# POWER_STAGE.net
KiCad netlist of a schematic drawn in Altium Designer
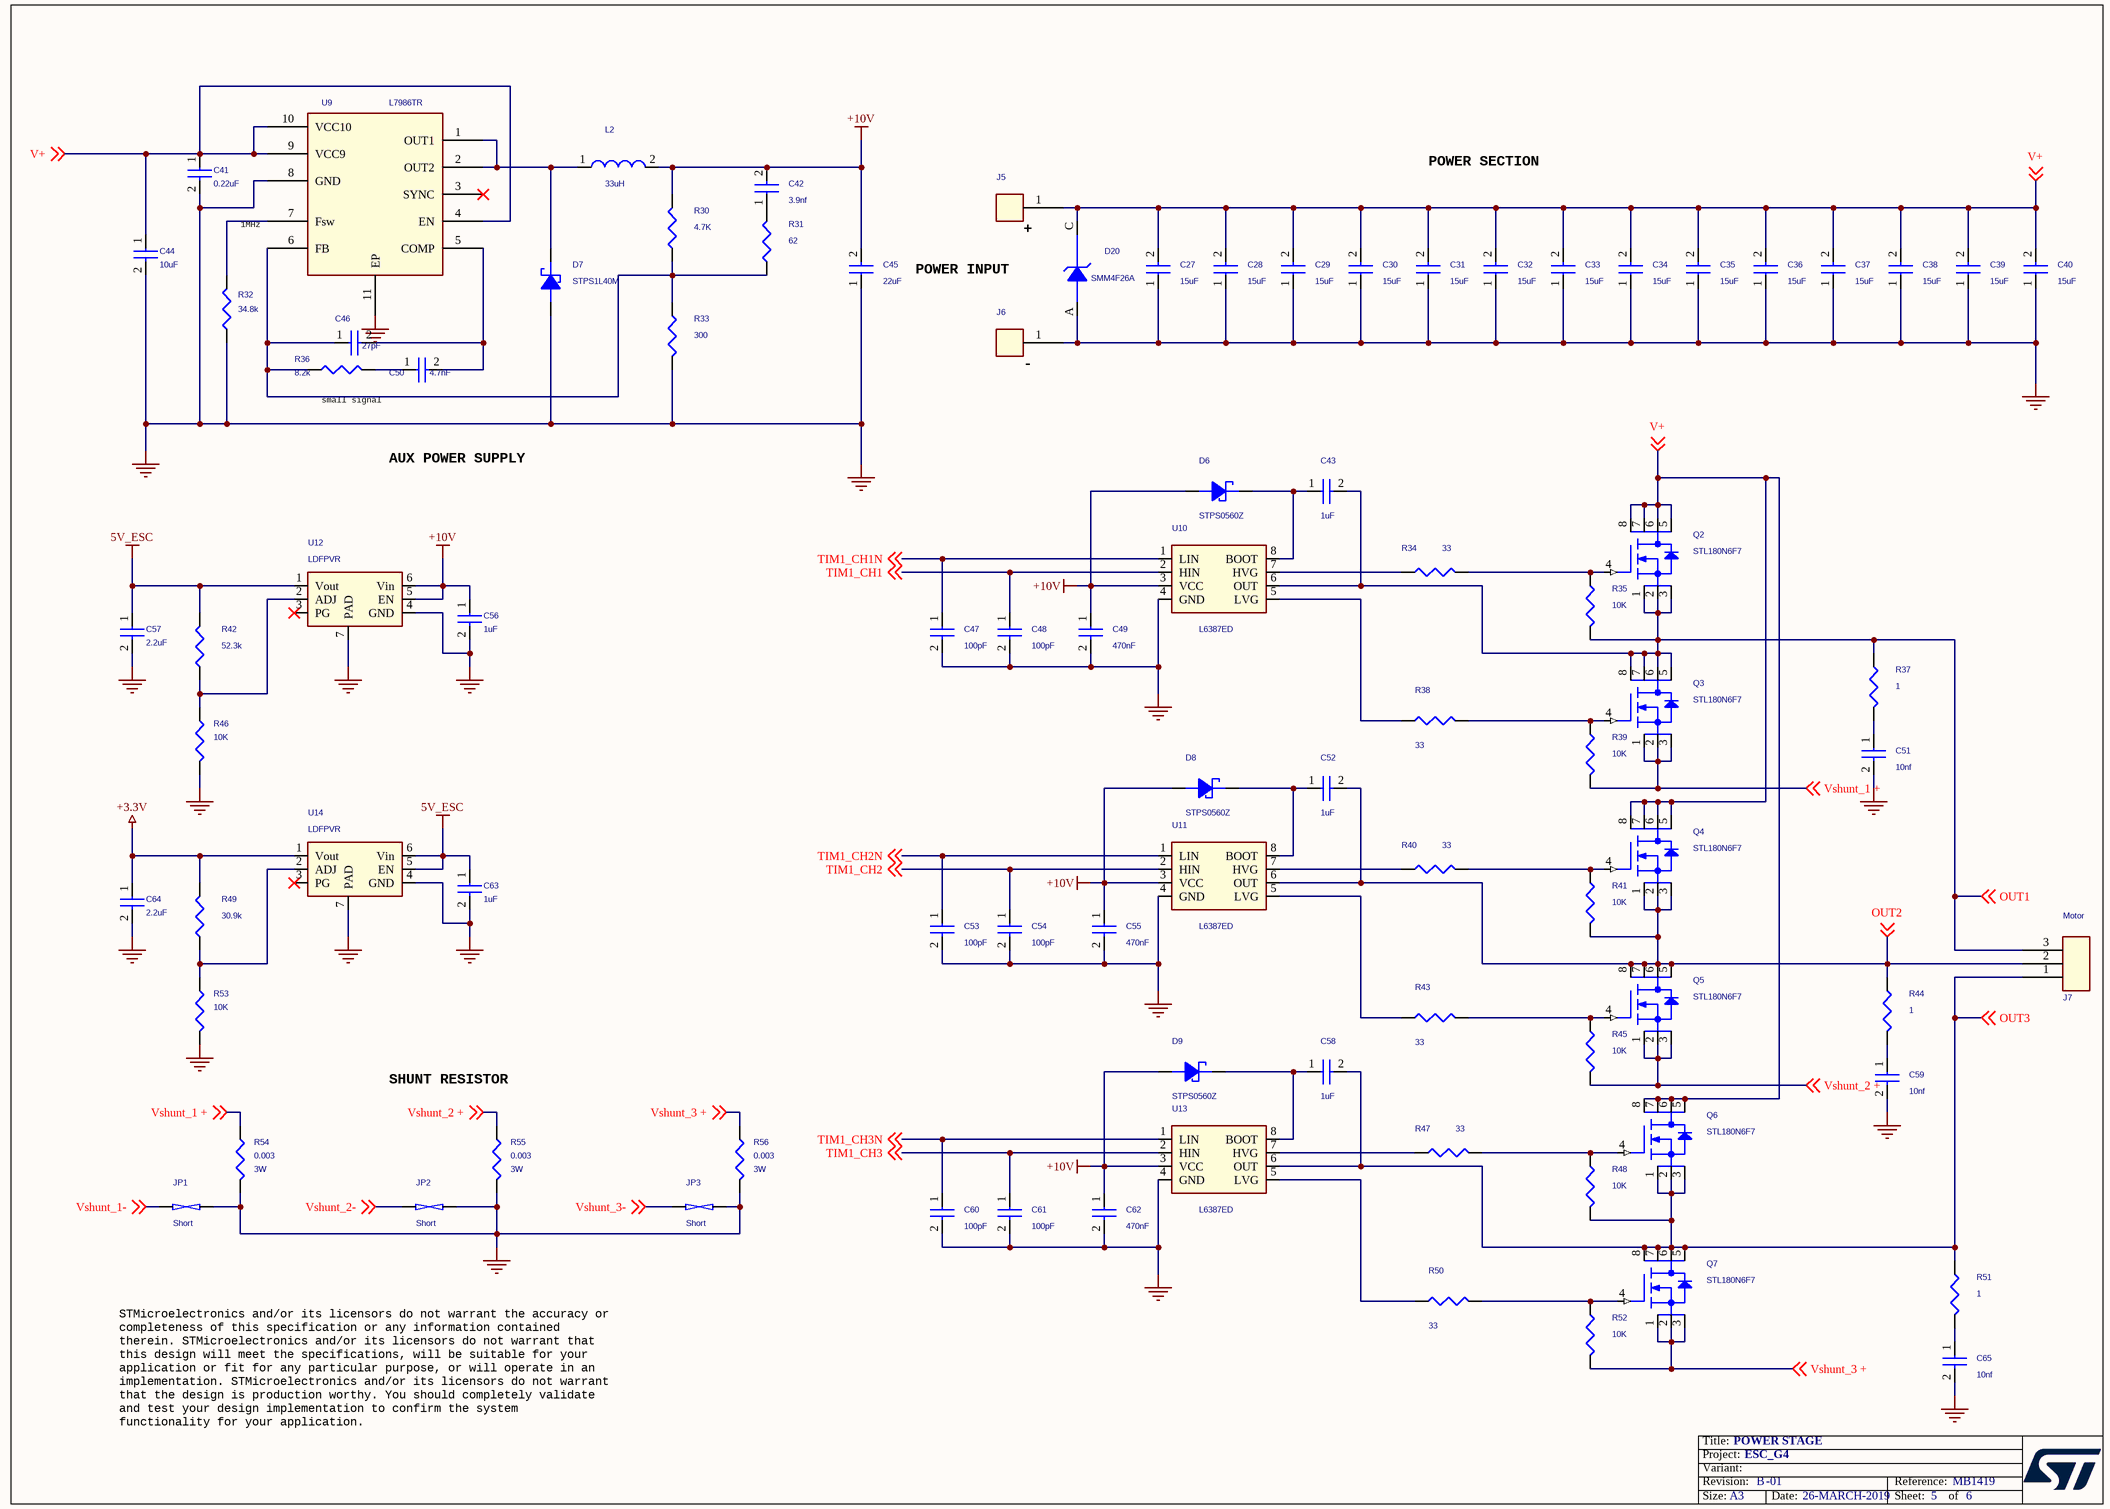
[diagram p0: POWER STAGE.SchDoc]

(export (version "E")
  (design (tool "Eeschema 10.0.6"))
  (components
    (comp (ref "C27")
      (value "15uF")
      (footprint "C_0805_HD")
      (description "CAP CER 15UF 35V X5R 0805")
      (fields (field (name "PART_NUMBER") "TMP-773") (field (name "TOLERANCE") "20%"))
      (libsource (lib "*") (part "CAP_Dup1"))
    )
    (comp (ref "C28")
      (value "15uF")
      (footprint "C_0805_HD")
      (description "CAP CER 15UF 35V X5R 0805")
      (fields (field (name "PART_NUMBER") "TMP-773") (field (name "TOLERANCE") "20%"))
      (libsource (lib "*") (part "CAP_Dup1"))
    )
    (comp (ref "C29")
      (value "15uF")
      (footprint "C_0805_HD")
      (description "CAP CER 15UF 35V X5R 0805")
      (fields (field (name "PART_NUMBER") "TMP-773") (field (name "TOLERANCE") "20%"))
      (libsource (lib "*") (part "CAP_Dup1"))
    )
    (comp (ref "C30")
      (value "15uF")
      (footprint "C_0805_HD")
      (description "CAP CER 15UF 35V X5R 0805")
      (fields (field (name "PART_NUMBER") "TMP-773") (field (name "TOLERANCE") "20%"))
      (libsource (lib "*") (part "CAP_Dup1"))
    )
    (comp (ref "C31")
      (value "15uF")
      (footprint "C_0805_HD")
      (description "CAP CER 15UF 35V X5R 0805")
      (fields (field (name "PART_NUMBER") "TMP-773") (field (name "TOLERANCE") "20%"))
      (libsource (lib "*") (part "CAP_Dup1"))
    )
    (comp (ref "C32")
      (value "15uF")
      (footprint "C_0805_HD")
      (description "CAP CER 15UF 35V X5R 0805")
      (fields (field (name "PART_NUMBER") "TMP-773") (field (name "TOLERANCE") "20%"))
      (libsource (lib "*") (part "CAP_Dup1"))
    )
    (comp (ref "C33")
      (value "15uF")
      (footprint "C_0805_HD")
      (description "CAP CER 15UF 35V X5R 0805")
      (fields (field (name "PART_NUMBER") "TMP-773") (field (name "TOLERANCE") "20%"))
      (libsource (lib "*") (part "CAP_Dup1"))
    )
    (comp (ref "C34")
      (value "15uF")
      (footprint "C_0805_HD")
      (description "CAP CER 15UF 35V X5R 0805")
      (fields (field (name "PART_NUMBER") "TMP-773") (field (name "TOLERANCE") "20%"))
      (libsource (lib "*") (part "CAP_Dup1"))
    )
    (comp (ref "C35")
      (value "15uF")
      (footprint "C_0805_HD")
      (description "CAP CER 15UF 35V X5R 0805")
      (fields (field (name "PART_NUMBER") "TMP-773") (field (name "TOLERANCE") "20%"))
      (libsource (lib "*") (part "CAP_Dup1"))
    )
    (comp (ref "C36")
      (value "15uF")
      (footprint "C_0805_HD")
      (description "CAP CER 15UF 35V X5R 0805")
      (fields (field (name "PART_NUMBER") "TMP-773") (field (name "TOLERANCE") "20%"))
      (libsource (lib "*") (part "CAP_Dup1"))
    )
    (comp (ref "C37")
      (value "15uF")
      (footprint "C_0805_HD")
      (description "CAP CER 15UF 35V X5R 0805")
      (fields (field (name "PART_NUMBER") "TMP-773") (field (name "TOLERANCE") "20%"))
      (libsource (lib "*") (part "CAP_Dup1"))
    )
    (comp (ref "C38")
      (value "15uF")
      (footprint "C_0805_HD")
      (description "CAP CER 15UF 35V X5R 0805")
      (fields (field (name "PART_NUMBER") "TMP-773") (field (name "TOLERANCE") "20%"))
      (libsource (lib "*") (part "CAP_Dup1"))
    )
    (comp (ref "C39")
      (value "15uF")
      (footprint "C_0805_HD")
      (description "CAP CER 15UF 35V X5R 0805")
      (fields (field (name "PART_NUMBER") "TMP-773") (field (name "TOLERANCE") "20%"))
      (libsource (lib "*") (part "CAP_Dup1"))
    )
    (comp (ref "C40")
      (value "15uF")
      (footprint "C_0805_HD")
      (description "CAP CER 15UF 35V X5R 0805")
      (fields (field (name "PART_NUMBER") "TMP-773") (field (name "TOLERANCE") "20%"))
      (libsource (lib "*") (part "CAP_Dup1"))
    )
    (comp (ref "C41")
      (value "0.22uF")
      (footprint "C_0603_HD")
      (description "CAP CER 0.22UF 50V X7R 0603")
      (fields (field (name "MANUFACTURER") "TDK Corporation") (field (name "TOLERANCE") "10%"))
      (libsource (lib "*") (part "CAP_Dup1"))
    )
    (comp (ref "C42")
      (value "3.9nf")
      (footprint "C_0402")
      (description "CAP CER 3900PF 16V X7R 0402")
      (fields (field (name "MANUFACTURER") "KEMET") (field (name "TOLERANCE") "10%"))
      (libsource (lib "*") (part "CAP_Dup1"))
    )
    (comp (ref "C43")
      (value "1uF")
      (footprint "C_0603_HD")
      (description "CAP CER 1UF 25V X7R 0603")
      (fields (field (name "PART_NUMBER") "TMP-446") (field (name "TOLERANCE") "10%"))
      (libsource (lib "*") (part "CAP_Dup1"))
    )
    (comp (ref "C44")
      (value "10uF")
      (footprint "C_1206")
      (description "CAP CER 10UF 50V X7R 1206")
      (fields
        (field (name "MANUFACTURER") "Samsung Electro-Mechanics America, Inc.")
        (field (name "TOLERANCE") "10%")
      )
      (libsource (lib "*") (part "CAP_Dup1"))
    )
    (comp (ref "C45")
      (value "22uF")
      (footprint "C_1206")
      (description "CAP CER 22UF 25V X5R 1206")
      (fields
        (field (name "MANUFACTURER") "Murata Electronics North America")
        (field (name "TOLERANCE") "20%")
      )
      (libsource (lib "*") (part "CAP_Dup1"))
    )
    (comp (ref "C46")
      (value "27pF")
      (footprint "C_0402")
      (description "CAP CER 27PF 25V C0G/NP0 0402")
      (fields
        (field (name "MANUFACTURER") "Murata Electronics North America")
        (field (name "TOLERANCE") "5%")
      )
      (libsource (lib "*") (part "CAP_Dup1"))
    )
    (comp (ref "C47")
      (value "100pF")
      (footprint "C_0402")
      (description "CAP CER 100PF 25V X7R 0402")
      (fields (field (name "PART_NUMBER") "TMP-426") (field (name "TOLERANCE") "10%"))
      (libsource (lib "*") (part "CAP_Dup1"))
    )
    (comp (ref "C48")
      (value "100pF")
      (footprint "C_0402")
      (description "CAP CER 100PF 25V X7R 0402")
      (fields (field (name "PART_NUMBER") "TMP-426") (field (name "TOLERANCE") "10%"))
      (libsource (lib "*") (part "CAP_Dup1"))
    )
    (comp (ref "C49")
      (value "470nF")
      (footprint "C_0603_HD")
      (description "CAP CER 0.47UF 25V X7R 0603")
      (fields (field (name "PART_NUMBER") "TMP-428") (field (name "TOLERANCE") "10%"))
      (libsource (lib "*") (part "CAP_Dup1"))
    )
    (comp (ref "C50")
      (value "4.7nF")
      (footprint "C_0402")
      (description "CAP CER 4700PF 16V X7R 0402")
      (fields (field (name "MANUFACTURER") "Wurth Electronics Inc.") (field (name "TOLERANCE") "10%"))
      (libsource (lib "*") (part "CAP_Dup1"))
    )
    (comp (ref "C51")
      (value "10nf")
      (footprint "C_0603")
      (description "CAP CER 10000PF 100V X7R 0603")
      (fields (field (name "PART_NUMBER") "CAP-00000040") (field (name "TOLERANCE") "20%"))
      (libsource (lib "*") (part "CAP_Dup1"))
    )
    (comp (ref "C52")
      (value "1uF")
      (footprint "C_0603_HD")
      (description "CAP CER 1UF 25V X7R 0603")
      (fields (field (name "PART_NUMBER") "TMP-446") (field (name "TOLERANCE") "10%"))
      (libsource (lib "*") (part "CAP_Dup1"))
    )
    (comp (ref "C53")
      (value "100pF")
      (footprint "C_0402")
      (description "CAP CER 100PF 25V X7R 0402")
      (fields (field (name "PART_NUMBER") "TMP-426") (field (name "TOLERANCE") "10%"))
      (libsource (lib "*") (part "CAP_Dup1"))
    )
    (comp (ref "C54")
      (value "100pF")
      (footprint "C_0402")
      (description "CAP CER 100PF 25V X7R 0402")
      (fields (field (name "PART_NUMBER") "TMP-426") (field (name "TOLERANCE") "10%"))
      (libsource (lib "*") (part "CAP_Dup1"))
    )
    (comp (ref "C55")
      (value "470nF")
      (footprint "C_0603_HD")
      (description "CAP CER 0.47UF 25V X7R 0603")
      (fields (field (name "PART_NUMBER") "TMP-428") (field (name "TOLERANCE") "10%"))
      (libsource (lib "*") (part "CAP_Dup1"))
    )
    (comp (ref "C56")
      (value "1uF")
      (footprint "C_0402")
      (description "CAP CER 1UF 25V X5R 0402")
      (fields
        (field (name "MANUFACTURER") "Murata Electronics North America")
        (field (name "TOLERANCE") "10%")
      )
      (libsource (lib "*") (part "CAP_Dup1"))
    )
    (comp (ref "C57")
      (value "2.2uF")
      (footprint "C_0402")
      (description "CAP CER 2.2UF 10V X5R 0402")
      (fields (field (name "PART_NUMBER") "TMP-449") (field (name "TOLERANCE") "20%"))
      (libsource (lib "*") (part "CAP_Dup1"))
    )
    (comp (ref "C58")
      (value "1uF")
      (footprint "C_0603_HD")
      (description "CAP CER 1UF 25V X7R 0603")
      (fields (field (name "PART_NUMBER") "TMP-446") (field (name "TOLERANCE") "10%"))
      (libsource (lib "*") (part "CAP_Dup1"))
    )
    (comp (ref "C59")
      (value "10nf")
      (footprint "C_0603")
      (description "CAP CER 10000PF 100V X7R 0603")
      (fields (field (name "PART_NUMBER") "CAP-00000040") (field (name "TOLERANCE") "20%"))
      (libsource (lib "*") (part "CAP_Dup1"))
    )
    (comp (ref "C60")
      (value "100pF")
      (footprint "C_0402")
      (description "CAP CER 100PF 25V X7R 0402")
      (fields (field (name "PART_NUMBER") "TMP-426") (field (name "TOLERANCE") "10%"))
      (libsource (lib "*") (part "CAP_Dup1"))
    )
    (comp (ref "C61")
      (value "100pF")
      (footprint "C_0402")
      (description "CAP CER 100PF 25V X7R 0402")
      (fields (field (name "PART_NUMBER") "TMP-426") (field (name "TOLERANCE") "10%"))
      (libsource (lib "*") (part "CAP_Dup1"))
    )
    (comp (ref "C62")
      (value "470nF")
      (footprint "C_0603_HD")
      (description "CAP CER 0.47UF 25V X7R 0603")
      (fields (field (name "PART_NUMBER") "TMP-428") (field (name "TOLERANCE") "10%"))
      (libsource (lib "*") (part "CAP_Dup1"))
    )
    (comp (ref "C63")
      (value "1uF")
      (footprint "C_0402")
      (description "CAP CER 1UF 25V X5R 0402")
      (fields
        (field (name "MANUFACTURER") "Murata Electronics North America")
        (field (name "TOLERANCE") "10%")
      )
      (libsource (lib "*") (part "CAP_Dup1"))
    )
    (comp (ref "C64")
      (value "2.2uF")
      (footprint "C_0402")
      (description "CAP CER 2.2UF 10V X5R 0402")
      (fields (field (name "PART_NUMBER") "TMP-449") (field (name "TOLERANCE") "20%"))
      (libsource (lib "*") (part "CAP_Dup1"))
    )
    (comp (ref "C65")
      (value "10nf")
      (footprint "C_0603")
      (description "CAP CER 10000PF 100V X7R 0603")
      (fields (field (name "PART_NUMBER") "CAP-00000040") (field (name "TOLERANCE") "20%"))
      (libsource (lib "*") (part "CAP_Dup1"))
    )
    (comp (ref "D6")
      (value "STPS0560Z")
      (footprint "SOD_123")
      (description "DIODE SCHOTTKY 60V 500MA SOD123")
      (fields (field (name "MANUFACTURER") "STMicroelectronics") (field (name "PART_NUMBER") "TMP-373"))
      (libsource (lib "*") (part "DIODE_SCHOTTKY_0"))
    )
    (comp (ref "D7")
      (value "STPS1L40M")
      (footprint "do216-aa_stmite")
      (description "DIODE SCHOTTKY 40V 1A STMITE")
      (fields (field (name "PART_NUMBER") "TMP-372") (field (name "MANUFACTURER") "STMicroelectronics"))
      (libsource (lib "*") (part "DIODE_SCHOTTKY_0"))
    )
    (comp (ref "D8")
      (value "STPS0560Z")
      (footprint "SOD_123")
      (description "DIODE SCHOTTKY 60V 500MA SOD123")
      (fields (field (name "MANUFACTURER") "STMicroelectronics") (field (name "PART_NUMBER") "TMP-373"))
      (libsource (lib "*") (part "DIODE_SCHOTTKY_0"))
    )
    (comp (ref "D9")
      (value "STPS0560Z")
      (footprint "SOD_123")
      (description "DIODE SCHOTTKY 60V 500MA SOD123")
      (fields (field (name "MANUFACTURER") "STMicroelectronics") (field (name "PART_NUMBER") "TMP-373"))
      (libsource (lib "*") (part "DIODE_SCHOTTKY_0"))
    )
    (comp (ref "D20")
      (value "SMM4F26A")
      (footprint "do216-aa-flat")
      (description "TVS DIODE 26VWM 53.5VC DO222AA")
      (fields (field (name "MANUFACTURER") "STMicroelectronics") (field (name "PART_NUMBER") "TMP-376"))
      (libsource (lib "*") (part "DIODE_TRANSIL_UNI_0"))
    )
    (comp (ref "J5")
      (value "CON1")
      (footprint "wire1_220s")
      (description "SOLDER PADS")
      (libsource (lib "*") (part "CON1"))
    )
    (comp (ref "J6")
      (value "CON1")
      (footprint "wire1_220s")
      (description "SOLDER PADS")
      (libsource (lib "*") (part "CON1"))
    )
    (comp (ref "J7")
      (value "Motor")
      (footprint "conn_motor_out")
      (description "SOLDER PADS")
      (libsource (lib "*") (part "CON3"))
    )
    (comp (ref "JP1")
      (value "Short")
      (footprint "SHORT")
      (description "2 PIN SHORTED TO CONNECT DIFFERENT NETS")
      (fields (field (name "PART_NUMBER") "TMP-442"))
      (libsource (lib "*") (part "SHORT"))
    )
    (comp (ref "JP2")
      (value "Short")
      (footprint "SHORT")
      (description "2 PIN SHORTED TO CONNECT DIFFERENT NETS")
      (fields (field (name "PART_NUMBER") "TMP-442"))
      (libsource (lib "*") (part "SHORT"))
    )
    (comp (ref "JP3")
      (value "Short")
      (footprint "SHORT")
      (description "2 PIN SHORTED TO CONNECT DIFFERENT NETS")
      (fields (field (name "PART_NUMBER") "TMP-442"))
      (libsource (lib "*") (part "SHORT"))
    )
    (comp (ref "L2")
      (value "33uH")
      (footprint "ind_Coilcraft-LPS4018")
      (description "Fixed Inductors LPS4018 Low Profile 33uH 0.8A 20% SMD")
      (fields (field (name "MANUFACTURER") "Coilcraft") (field (name "TOLERANCE") "20%"))
      (libsource (lib "*") (part "IND"))
    )
    (comp (ref "Q2")
      (value "STL180N6F7")
      (footprint "power_flat_5x6")
      (description "N-channel 60 V, 1.9 mO typ., 120 A STripFET™ F7")
      (fields (field (name "PART_NUMBER") "TMP-772") (field (name "MANUFACTURER") "STMicroelectronics"))
      (libsource (lib "*") (part "MOSFET_N_DIODE_SSSGDDDD"))
    )
    (comp (ref "Q3")
      (value "STL180N6F7")
      (footprint "power_flat_5x6")
      (description "N-channel 60 V, 1.9 mO typ., 120 A STripFET™ F7")
      (fields (field (name "PART_NUMBER") "TMP-772") (field (name "MANUFACTURER") "STMicroelectronics"))
      (libsource (lib "*") (part "MOSFET_N_DIODE_SSSGDDDD"))
    )
    (comp (ref "Q4")
      (value "STL180N6F7")
      (footprint "power_flat_5x6")
      (description "N-channel 60 V, 1.9 mO typ., 120 A STripFET™ F7")
      (fields (field (name "PART_NUMBER") "TMP-772") (field (name "MANUFACTURER") "STMicroelectronics"))
      (libsource (lib "*") (part "MOSFET_N_DIODE_SSSGDDDD"))
    )
    (comp (ref "Q5")
      (value "STL180N6F7")
      (footprint "power_flat_5x6")
      (description "N-channel 60 V, 1.9 mO typ., 120 A STripFET™ F7")
      (fields (field (name "PART_NUMBER") "TMP-772") (field (name "MANUFACTURER") "STMicroelectronics"))
      (libsource (lib "*") (part "MOSFET_N_DIODE_SSSGDDDD"))
    )
    (comp (ref "Q6")
      (value "STL180N6F7")
      (footprint "power_flat_5x6")
      (description "N-channel 60 V, 1.9 mO typ., 120 A STripFET™ F7")
      (fields (field (name "PART_NUMBER") "TMP-772") (field (name "MANUFACTURER") "STMicroelectronics"))
      (libsource (lib "*") (part "MOSFET_N_DIODE_SSSGDDDD"))
    )
    (comp (ref "Q7")
      (value "STL180N6F7")
      (footprint "power_flat_5x6")
      (description "N-channel 60 V, 1.9 mO typ., 120 A STripFET™ F7")
      (fields (field (name "PART_NUMBER") "TMP-772") (field (name "MANUFACTURER") "STMicroelectronics"))
      (libsource (lib "*") (part "MOSFET_N_DIODE_SSSGDDDD"))
    )
    (comp (ref "R30")
      (value "4.7K")
      (footprint "R_0402")
      (description "RES SMD 4.7K OHM 1% 1/16W 0402")
      (fields (field (name "MANUFACTURER") "TE Connectivity Passive Product") (field (name "TOLERANCE") "1%"))
      (libsource (lib "*") (part "RES"))
    )
    (comp (ref "R31")
      (value "62")
      (footprint "R_0402")
      (description "RES SMD 62 OHM 1% 1/16W 0402")
      (fields (field (name "MANUFACTURER") "Yageo") (field (name "TOLERANCE") "1%"))
      (libsource (lib "*") (part "RES"))
    )
    (comp (ref "R32")
      (value "34.8k")
      (footprint "R_0402")
      (description "RES SMD 34.8K OHM 1% 1/16W 0402")
      (fields (field (name "MANUFACTURER") "Yageo") (field (name "TOLERANCE") "1%"))
      (libsource (lib "*") (part "RES"))
    )
    (comp (ref "R33")
      (value "300")
      (footprint "R_0402")
      (description "RES SMD 300 OHM 1% 1/16W 0402")
      (fields (field (name "PART_NUMBER") "TMP-418") (field (name "TOLERANCE") "1%"))
      (libsource (lib "*") (part "RES"))
    )
    (comp (ref "R34")
      (value "33")
      (footprint "R_0603_HD")
      (description "RES SMD 33 OHM 1% 1/10W 0603")
      (fields (field (name "MANUFACTURER") "Yageo") (field (name "TOLERANCE") "1%"))
      (libsource (lib "*") (part "RES"))
    )
    (comp (ref "R35")
      (value "10K")
      (footprint "R_0402")
      (description "RES SMD 10K OHM 1% 1/16W 0402")
      (fields (field (name "MANUFACTURER") "Yageo") (field (name "TOLERANCE") "1%"))
      (libsource (lib "*") (part "RES"))
    )
    (comp (ref "R36")
      (value "8.2k")
      (footprint "R_0402")
      (description "RES SMD 8.2K OHM 5% 1/16W 0402")
      (fields (field (name "MANUFACTURER") "Yageo") (field (name "TOLERANCE") "5%"))
      (libsource (lib "*") (part "RES"))
    )
    (comp (ref "R37")
      (value "1")
      (footprint "R_0805")
      (description "RES SMD 1 OHM 5% 1/8W 0805")
      (fields (field (name "PART_NUMBER") "TMP-430") (field (name "TOLERANCE") "5%"))
      (libsource (lib "*") (part "RES"))
    )
    (comp (ref "R38")
      (value "33")
      (footprint "R_0603_HD")
      (description "RES SMD 33 OHM 1% 1/10W 0603")
      (fields (field (name "PART_NUMBER") "TMP-266") (field (name "TOLERANCE") "1%"))
      (libsource (lib "*") (part "RES"))
    )
    (comp (ref "R39")
      (value "10K")
      (footprint "R_0402")
      (description "RES SMD 10K OHM 1% 1/16W 0402")
      (fields (field (name "MANUFACTURER") "Yageo") (field (name "TOLERANCE") "1%"))
      (libsource (lib "*") (part "RES"))
    )
    (comp (ref "R40")
      (value "33")
      (footprint "R_0603_HD")
      (description "RES SMD 33 OHM 1% 1/10W 0603")
      (fields (field (name "MANUFACTURER") "Yageo") (field (name "TOLERANCE") "1%"))
      (libsource (lib "*") (part "RES"))
    )
    (comp (ref "R41")
      (value "10K")
      (footprint "R_0402")
      (description "RES SMD 10K OHM 1% 1/16W 0402")
      (fields (field (name "MANUFACTURER") "Yageo") (field (name "TOLERANCE") "1%"))
      (libsource (lib "*") (part "RES"))
    )
    (comp (ref "R42")
      (value "52.3k")
      (footprint "R_0402")
      (description "RES SMD 52.3K OHM 1% 1/16W 0402")
      (fields (field (name "MANUFACTURER") "Samsung Electro-Mechanics") (field (name "TOLERANCE") "1%"))
      (libsource (lib "*") (part "RES"))
    )
    (comp (ref "R43")
      (value "33")
      (footprint "R_0603_HD")
      (description "RES SMD 33 OHM 1% 1/10W 0603")
      (fields (field (name "PART_NUMBER") "TMP-266") (field (name "TOLERANCE") "1%"))
      (libsource (lib "*") (part "RES"))
    )
    (comp (ref "R44")
      (value "1")
      (footprint "R_0805")
      (description "RES SMD 1 OHM 5% 1/8W 0805")
      (fields (field (name "PART_NUMBER") "TMP-430") (field (name "TOLERANCE") "5%"))
      (libsource (lib "*") (part "RES"))
    )
    (comp (ref "R45")
      (value "10K")
      (footprint "R_0402")
      (description "RES SMD 10K OHM 1% 1/16W 0402")
      (fields (field (name "MANUFACTURER") "Yageo") (field (name "TOLERANCE") "1%"))
      (libsource (lib "*") (part "RES"))
    )
    (comp (ref "R46")
      (value "10K")
      (footprint "R_0402")
      (description "RES SMD 10K OHM 1% 1/16W 0402")
      (fields (field (name "PART_NUMBER") "TMP-396") (field (name "TOLERANCE") "1%"))
      (libsource (lib "*") (part "RES"))
    )
    (comp (ref "R47")
      (value "33")
      (footprint "R_0603_HD")
      (description "RES SMD 33 OHM 1% 1/10W 0603")
      (fields (field (name "PART_NUMBER") "TMP-266") (field (name "TOLERANCE") "1%"))
      (libsource (lib "*") (part "RES"))
    )
    (comp (ref "R48")
      (value "10K")
      (footprint "R_0402")
      (description "RES SMD 10K OHM 1% 1/16W 0402")
      (fields (field (name "PART_NUMBER") "TMP-396") (field (name "TOLERANCE") "1%"))
      (libsource (lib "*") (part "RES"))
    )
    (comp (ref "R49")
      (value "30.9k")
      (footprint "R_0402")
      (description "RES SMD 30.9K OHM 1% 1/10W 0402")
      (fields (field (name "PART_NUMBER") "TMP-448") (field (name "TOLERANCE") "1%"))
      (libsource (lib "*") (part "RES"))
    )
    (comp (ref "R50")
      (value "33")
      (footprint "R_0603_HD")
      (description "RES SMD 33 OHM 1% 1/10W 0603")
      (fields (field (name "PART_NUMBER") "TMP-266") (field (name "TOLERANCE") "1%"))
      (libsource (lib "*") (part "RES"))
    )
    (comp (ref "R51")
      (value "1")
      (footprint "R_0805")
      (description "RES SMD 1 OHM 5% 1/8W 0805")
      (fields (field (name "PART_NUMBER") "TMP-430") (field (name "TOLERANCE") "5%"))
      (libsource (lib "*") (part "RES"))
    )
    (comp (ref "R52")
      (value "10K")
      (footprint "R_0402")
      (description "RES SMD 10K OHM 1% 1/16W 0402")
      (fields (field (name "PART_NUMBER") "TMP-396") (field (name "TOLERANCE") "1%"))
      (libsource (lib "*") (part "RES"))
    )
    (comp (ref "R53")
      (value "10K")
      (footprint "R_0402")
      (description "RES SMD 10K OHM 1% 1/16W 0402")
      (fields (field (name "PART_NUMBER") "TMP-396") (field (name "TOLERANCE") "1%"))
      (libsource (lib "*") (part "RES"))
    )
    (comp (ref "R54")
      (value "0.003")
      (footprint "resc635x300x60l193n")
      (description "RES 0.003 OHM 1% 3W 2512")
      (fields
        (field (name "PART_NUMBER") "TMP-766")
        (field (name "TOLERANCE") "1%")
        (field (name "RATED POWER") "3W")
      )
      (libsource (lib "*") (part "RES"))
    )
    (comp (ref "R55")
      (value "0.003")
      (footprint "resc635x300x60l193n")
      (description "RES 0.003 OHM 1% 3W 2512")
      (fields
        (field (name "MANUFACTURER") "TE Connectivity Passive Product")
        (field (name "RATED POWER") "3W")
        (field (name "TOLERANCE") "1%")
      )
      (libsource (lib "*") (part "RES"))
    )
    (comp (ref "R56")
      (value "0.003")
      (footprint "resc635x300x60l193n")
      (description "RES 0.003 OHM 1% 3W 2512")
      (fields
        (field (name "PART_NUMBER") "TMP-766")
        (field (name "TOLERANCE") "1%")
        (field (name "RATED POWER") "3W")
      )
      (libsource (lib "*") (part "RES"))
    )
    (comp (ref "U9")
      (value "L7986TR")
      (footprint "son11p50_300x300x100l40x24t2-1")
      (description "IC REG BUCK ADJ 3A 10VDFPN")
      (fields (field (name "MANUFACTURER") "STMicroelectronics") (field (name "PART_NUMBER") "TMP-362"))
      (libsource (lib "*") (part "L7986TR"))
    )
    (comp (ref "U10")
      (value "L6387ED")
      (footprint "SOIC8P127_490X600X175L83X42N")
      (description "IC DRIVER HI/LO SIDE HV 8-SOIC")
      (fields (field (name "MANUFACTURER") "STMicroelectronics") (field (name "PART_NUMBER") "TMP-367"))
      (libsource (lib "*") (part "L6387E"))
    )
    (comp (ref "U11")
      (value "L6387ED")
      (footprint "SOIC8P127_490X600X175L83X42N")
      (description "IC DRIVER HI/LO SIDE HV 8-SOIC")
      (fields (field (name "PART_NUMBER") "TMP-367") (field (name "MANUFACTURER") "STMicroelectronics"))
      (libsource (lib "*") (part "L6387E"))
    )
    (comp (ref "U12")
      (value "LDFPVR")
      (footprint "son7p65_200x200x100l25x30t18-1")
      (description "IC REG LINEAR POS ADJ 1A 6DFN")
      (fields (field (name "PART_NUMBER") "TMP-450") (field (name "MANUFACTURER") "STMicroelectronics"))
      (libsource (lib "*") (part "LDFPxR"))
    )
    (comp (ref "U13")
      (value "L6387ED")
      (footprint "SOIC8P127_490X600X175L83X42N")
      (description "IC DRIVER HI/LO SIDE HV 8-SOIC")
      (fields (field (name "PART_NUMBER") "TMP-367") (field (name "MANUFACTURER") "STMicroelectronics"))
      (libsource (lib "*") (part "L6387E"))
    )
    (comp (ref "U14")
      (value "LDFPVR")
      (footprint "son7p65_200x200x100l25x30t18-1")
      (description "IC REG LINEAR POS ADJ 1A 6DFN")
      (fields (field (name "MANUFACTURER") "STMicroelectronics") (field (name "PART_NUMBER") "TMP-450"))
      (libsource (lib "*") (part "LDFPxR"))
    )
  )
  (nets
    (net (code "1") (name "+3.3V") (class "Default")
      (node (ref "C64") (pin "1") (pinfunction "1_1") (pintype "passive"))
      (node (ref "R49") (pin "2") (pinfunction "2_2") (pintype "passive"))
      (node (ref "U14") (pin "1") (pinfunction "Vout_1") (pintype "passive"))
    )
    (net (code "2") (name "+10V") (class "Default")
      (node (ref "C42") (pin "2") (pinfunction "2_2") (pintype "passive"))
      (node (ref "C45") (pin "2") (pinfunction "2_2") (pintype "passive"))
      (node (ref "C49") (pin "1") (pinfunction "1_1") (pintype "passive"))
      (node (ref "C55") (pin "1") (pinfunction "1_1") (pintype "passive"))
      (node (ref "C56") (pin "1") (pinfunction "1_1") (pintype "passive"))
      (node (ref "C62") (pin "1") (pinfunction "1_1") (pintype "passive"))
      (node (ref "D6") (pin "A") (pinfunction "A_A") (pintype "passive"))
      (node (ref "D8") (pin "A") (pinfunction "A_A") (pintype "passive"))
      (node (ref "D9") (pin "A") (pinfunction "A_A") (pintype "passive"))
      (node (ref "L2") (pin "2") (pinfunction "2_2") (pintype "passive"))
      (node (ref "R30") (pin "1") (pinfunction "1_1") (pintype "passive"))
      (node (ref "U10") (pin "3") (pinfunction "VCC_3") (pintype "passive"))
      (node (ref "U11") (pin "3") (pinfunction "VCC_3") (pintype "passive"))
      (node (ref "U12") (pin "5") (pinfunction "EN_5") (pintype "passive"))
      (node (ref "U12") (pin "6") (pinfunction "Vin_6") (pintype "passive"))
      (node (ref "U13") (pin "3") (pinfunction "VCC_3") (pintype "passive"))
    )
    (net (code "3") (name "5V_ESC") (class "Default")
      (node (ref "C57") (pin "1") (pinfunction "1_1") (pintype "passive"))
      (node (ref "C63") (pin "1") (pinfunction "1_1") (pintype "passive"))
      (node (ref "R42") (pin "2") (pinfunction "2_2") (pintype "passive"))
      (node (ref "U12") (pin "1") (pinfunction "Vout_1") (pintype "passive"))
      (node (ref "U14") (pin "5") (pinfunction "EN_5") (pintype "passive"))
      (node (ref "U14") (pin "6") (pinfunction "Vin_6") (pintype "passive"))
    )
    (net (code "4") (name "GND") (class "Default")
      (node (ref "C27") (pin "1") (pinfunction "1_1") (pintype "passive"))
      (node (ref "C28") (pin "1") (pinfunction "1_1") (pintype "passive"))
      (node (ref "C29") (pin "1") (pinfunction "1_1") (pintype "passive"))
      (node (ref "C30") (pin "1") (pinfunction "1_1") (pintype "passive"))
      (node (ref "C31") (pin "1") (pinfunction "1_1") (pintype "passive"))
      (node (ref "C32") (pin "1") (pinfunction "1_1") (pintype "passive"))
      (node (ref "C33") (pin "1") (pinfunction "1_1") (pintype "passive"))
      (node (ref "C34") (pin "1") (pinfunction "1_1") (pintype "passive"))
      (node (ref "C35") (pin "1") (pinfunction "1_1") (pintype "passive"))
      (node (ref "C36") (pin "1") (pinfunction "1_1") (pintype "passive"))
      (node (ref "C37") (pin "1") (pinfunction "1_1") (pintype "passive"))
      (node (ref "C38") (pin "1") (pinfunction "1_1") (pintype "passive"))
      (node (ref "C39") (pin "1") (pinfunction "1_1") (pintype "passive"))
      (node (ref "C40") (pin "1") (pinfunction "1_1") (pintype "passive"))
      (node (ref "C41") (pin "2") (pinfunction "2_2") (pintype "passive"))
      (node (ref "C44") (pin "2") (pinfunction "2_2") (pintype "passive"))
      (node (ref "C45") (pin "1") (pinfunction "1_1") (pintype "passive"))
      (node (ref "C47") (pin "2") (pinfunction "2_2") (pintype "passive"))
      (node (ref "C48") (pin "2") (pinfunction "2_2") (pintype "passive"))
      (node (ref "C49") (pin "2") (pinfunction "2_2") (pintype "passive"))
      (node (ref "C51") (pin "2") (pinfunction "2_2") (pintype "passive"))
      (node (ref "C53") (pin "2") (pinfunction "2_2") (pintype "passive"))
      (node (ref "C54") (pin "2") (pinfunction "2_2") (pintype "passive"))
      (node (ref "C55") (pin "2") (pinfunction "2_2") (pintype "passive"))
      (node (ref "C56") (pin "2") (pinfunction "2_2") (pintype "passive"))
      (node (ref "C57") (pin "2") (pinfunction "2_2") (pintype "passive"))
      (node (ref "C59") (pin "2") (pinfunction "2_2") (pintype "passive"))
      (node (ref "C60") (pin "2") (pinfunction "2_2") (pintype "passive"))
      (node (ref "C61") (pin "2") (pinfunction "2_2") (pintype "passive"))
      (node (ref "C62") (pin "2") (pinfunction "2_2") (pintype "passive"))
      (node (ref "C63") (pin "2") (pinfunction "2_2") (pintype "passive"))
      (node (ref "C64") (pin "2") (pinfunction "2_2") (pintype "passive"))
      (node (ref "C65") (pin "2") (pinfunction "2_2") (pintype "passive"))
      (node (ref "D20") (pin "A") (pinfunction "A_A") (pintype "passive"))
      (node (ref "D7") (pin "A") (pinfunction "A_A") (pintype "passive"))
      (node (ref "J6") (pin "1") (pinfunction "1_1") (pintype "passive"))
      (node (ref "JP1") (pin "2") (pinfunction "2_2") (pintype "passive"))
      (node (ref "JP2") (pin "2") (pinfunction "2_2") (pintype "passive"))
      (node (ref "JP3") (pin "2") (pinfunction "2_2") (pintype "passive"))
      (node (ref "R32") (pin "2") (pinfunction "2_2") (pintype "passive"))
      (node (ref "R33") (pin "1") (pinfunction "1_1") (pintype "passive"))
      (node (ref "R46") (pin "2") (pinfunction "2_2") (pintype "passive"))
      (node (ref "R53") (pin "2") (pinfunction "2_2") (pintype "passive"))
      (node (ref "R54") (pin "2") (pinfunction "2_2") (pintype "passive"))
      (node (ref "R55") (pin "2") (pinfunction "2_2") (pintype "passive"))
      (node (ref "R56") (pin "2") (pinfunction "2_2") (pintype "passive"))
      (node (ref "U10") (pin "4") (pinfunction "GND_4") (pintype "passive"))
      (node (ref "U11") (pin "4") (pinfunction "GND_4") (pintype "passive"))
      (node (ref "U12") (pin "4") (pinfunction "GND_4") (pintype "passive"))
      (node (ref "U12") (pin "7") (pinfunction "PAD_7") (pintype "passive"))
      (node (ref "U13") (pin "4") (pinfunction "GND_4") (pintype "passive"))
      (node (ref "U14") (pin "4") (pinfunction "GND_4") (pintype "passive"))
      (node (ref "U14") (pin "7") (pinfunction "PAD_7") (pintype "passive"))
      (node (ref "U9") (pin "11") (pinfunction "EP_11") (pintype "passive"))
      (node (ref "U9") (pin "8") (pinfunction "GND_8") (pintype "passive"))
    )
    (net (code "5") (name "Net-(C42-Pad1)") (class "Default")
      (node (ref "C42") (pin "1") (pinfunction "1_1") (pintype "passive"))
      (node (ref "R31") (pin "1") (pinfunction "1_1") (pintype "passive"))
    )
    (net (code "6") (name "Net-(C50-Pad1)") (class "Default")
      (node (ref "C50") (pin "1") (pinfunction "1_1") (pintype "passive"))
      (node (ref "R36") (pin "1") (pinfunction "1_1") (pintype "passive"))
    )
    (net (code "7") (name "Net-(C51-Pad1)") (class "Default")
      (node (ref "C51") (pin "1") (pinfunction "1_1") (pintype "passive"))
      (node (ref "R37") (pin "2") (pinfunction "2_2") (pintype "passive"))
    )
    (net (code "8") (name "Net-(C59-Pad1)") (class "Default")
      (node (ref "C59") (pin "1") (pinfunction "1_1") (pintype "passive"))
      (node (ref "R44") (pin "2") (pinfunction "2_2") (pintype "passive"))
    )
    (net (code "9") (name "Net-(C65-Pad1)") (class "Default")
      (node (ref "C65") (pin "1") (pinfunction "1_1") (pintype "passive"))
      (node (ref "R51") (pin "2") (pinfunction "2_2") (pintype "passive"))
    )
    (net (code "10") (name "Net-(Q2-G)") (class "Default")
      (node (ref "Q2") (pin "4") (pinfunction "G_4") (pintype "input"))
      (node (ref "R34") (pin "2") (pinfunction "2_2") (pintype "passive"))
      (node (ref "R35") (pin "1") (pinfunction "1_1") (pintype "passive"))
    )
    (net (code "11") (name "Net-(Q3-G)") (class "Default")
      (node (ref "Q3") (pin "4") (pinfunction "G_4") (pintype "input"))
      (node (ref "R38") (pin "2") (pinfunction "2_2") (pintype "passive"))
      (node (ref "R39") (pin "1") (pinfunction "1_1") (pintype "passive"))
    )
    (net (code "12") (name "Net-(Q4-G)") (class "Default")
      (node (ref "Q4") (pin "4") (pinfunction "G_4") (pintype "input"))
      (node (ref "R40") (pin "2") (pinfunction "2_2") (pintype "passive"))
      (node (ref "R41") (pin "1") (pinfunction "1_1") (pintype "passive"))
    )
    (net (code "13") (name "Net-(Q5-G)") (class "Default")
      (node (ref "Q5") (pin "4") (pinfunction "G_4") (pintype "input"))
      (node (ref "R43") (pin "2") (pinfunction "2_2") (pintype "passive"))
      (node (ref "R45") (pin "1") (pinfunction "1_1") (pintype "passive"))
    )
    (net (code "14") (name "Net-(Q6-G)") (class "Default")
      (node (ref "Q6") (pin "4") (pinfunction "G_4") (pintype "input"))
      (node (ref "R47") (pin "2") (pinfunction "2_2") (pintype "passive"))
      (node (ref "R48") (pin "1") (pinfunction "1_1") (pintype "passive"))
    )
    (net (code "15") (name "Net-(Q7-G)") (class "Default")
      (node (ref "Q7") (pin "4") (pinfunction "G_4") (pintype "input"))
      (node (ref "R50") (pin "2") (pinfunction "2_2") (pintype "passive"))
      (node (ref "R52") (pin "1") (pinfunction "1_1") (pintype "passive"))
    )
    (net (code "16") (name "Net-(U9-COMP)") (class "Default")
      (node (ref "C46") (pin "2") (pinfunction "2_2") (pintype "passive"))
      (node (ref "C50") (pin "2") (pinfunction "2_2") (pintype "passive"))
      (node (ref "U9") (pin "5") (pinfunction "COMP_5") (pintype "passive"))
    )
    (net (code "17") (name "Net-(U9-FB)") (class "Default")
      (node (ref "C46") (pin "1") (pinfunction "1_1") (pintype "passive"))
      (node (ref "R30") (pin "2") (pinfunction "2_2") (pintype "passive"))
      (node (ref "R31") (pin "2") (pinfunction "2_2") (pintype "passive"))
      (node (ref "R33") (pin "2") (pinfunction "2_2") (pintype "passive"))
      (node (ref "R36") (pin "2") (pinfunction "2_2") (pintype "passive"))
      (node (ref "U9") (pin "6") (pinfunction "FB_6") (pintype "passive"))
    )
    (net (code "18") (name "Net-(U9-Fsw)") (class "Default")
      (node (ref "R32") (pin "1") (pinfunction "1_1") (pintype "passive"))
      (node (ref "U9") (pin "7") (pinfunction "Fsw_7") (pintype "passive"))
    )
    (net (code "19") (name "Net-(U9-OUT1)") (class "Default")
      (node (ref "D7") (pin "C") (pinfunction "C_C") (pintype "passive"))
      (node (ref "L2") (pin "1") (pinfunction "1_1") (pintype "passive"))
      (node (ref "U9") (pin "1") (pinfunction "OUT1_1") (pintype "passive"))
      (node (ref "U9") (pin "2") (pinfunction "OUT2_2") (pintype "passive"))
    )
    (net (code "20") (name "Net-(U10-BOOT)") (class "Default")
      (node (ref "C43") (pin "1") (pinfunction "1_1") (pintype "passive"))
      (node (ref "D6") (pin "C") (pinfunction "C_C") (pintype "passive"))
      (node (ref "U10") (pin "8") (pinfunction "BOOT_8") (pintype "passive"))
    )
    (net (code "21") (name "Net-(U10-HVG)") (class "Default")
      (node (ref "R34") (pin "1") (pinfunction "1_1") (pintype "passive"))
      (node (ref "U10") (pin "7") (pinfunction "HVG_7") (pintype "passive"))
    )
    (net (code "22") (name "Net-(U10-LVG)") (class "Default")
      (node (ref "R38") (pin "1") (pinfunction "1_1") (pintype "passive"))
      (node (ref "U10") (pin "5") (pinfunction "LVG_5") (pintype "passive"))
    )
    (net (code "23") (name "Net-(U11-BOOT)") (class "Default")
      (node (ref "C52") (pin "1") (pinfunction "1_1") (pintype "passive"))
      (node (ref "D8") (pin "C") (pinfunction "C_C") (pintype "passive"))
      (node (ref "U11") (pin "8") (pinfunction "BOOT_8") (pintype "passive"))
    )
    (net (code "24") (name "Net-(U11-HVG)") (class "Default")
      (node (ref "R40") (pin "1") (pinfunction "1_1") (pintype "passive"))
      (node (ref "U11") (pin "7") (pinfunction "HVG_7") (pintype "passive"))
    )
    (net (code "25") (name "Net-(U11-LVG)") (class "Default")
      (node (ref "R43") (pin "1") (pinfunction "1_1") (pintype "passive"))
      (node (ref "U11") (pin "5") (pinfunction "LVG_5") (pintype "passive"))
    )
    (net (code "26") (name "Net-(U12-ADJ)") (class "Default")
      (node (ref "R42") (pin "1") (pinfunction "1_1") (pintype "passive"))
      (node (ref "R46") (pin "1") (pinfunction "1_1") (pintype "passive"))
      (node (ref "U12") (pin "2") (pinfunction "ADJ_2") (pintype "passive"))
    )
    (net (code "27") (name "Net-(U13-BOOT)") (class "Default")
      (node (ref "C58") (pin "1") (pinfunction "1_1") (pintype "passive"))
      (node (ref "D9") (pin "C") (pinfunction "C_C") (pintype "passive"))
      (node (ref "U13") (pin "8") (pinfunction "BOOT_8") (pintype "passive"))
    )
    (net (code "28") (name "Net-(U13-HVG)") (class "Default")
      (node (ref "R47") (pin "1") (pinfunction "1_1") (pintype "passive"))
      (node (ref "U13") (pin "7") (pinfunction "HVG_7") (pintype "passive"))
    )
    (net (code "29") (name "Net-(U13-LVG)") (class "Default")
      (node (ref "R50") (pin "1") (pinfunction "1_1") (pintype "passive"))
      (node (ref "U13") (pin "5") (pinfunction "LVG_5") (pintype "passive"))
    )
    (net (code "30") (name "Net-(U14-ADJ)") (class "Default")
      (node (ref "R49") (pin "1") (pinfunction "1_1") (pintype "passive"))
      (node (ref "R53") (pin "1") (pinfunction "1_1") (pintype "passive"))
      (node (ref "U14") (pin "2") (pinfunction "ADJ_2") (pintype "passive"))
    )
    (net (code "31") (name "OUT1") (class "Default")
      (node (ref "C43") (pin "2") (pinfunction "2_2") (pintype "passive"))
      (node (ref "J7") (pin "3") (pinfunction "3_3") (pintype "passive"))
      (node (ref "Q2") (pin "1") (pinfunction "S1_1") (pintype "passive"))
      (node (ref "Q2") (pin "2") (pinfunction "S2_2") (pintype "passive"))
      (node (ref "Q2") (pin "3") (pinfunction "S3_3") (pintype "passive"))
      (node (ref "Q3") (pin "5") (pinfunction "D_5") (pintype "passive"))
      (node (ref "Q3") (pin "6") (pinfunction "D6_6") (pintype "passive"))
      (node (ref "Q3") (pin "7") (pinfunction "D7_7") (pintype "passive"))
      (node (ref "Q3") (pin "8") (pinfunction "D8_8") (pintype "passive"))
      (node (ref "R35") (pin "2") (pinfunction "2_2") (pintype "passive"))
      (node (ref "R37") (pin "1") (pinfunction "1_1") (pintype "passive"))
      (node (ref "U10") (pin "6") (pinfunction "OUT_6") (pintype "passive"))
    )
    (net (code "32") (name "OUT2") (class "Default")
      (node (ref "C52") (pin "2") (pinfunction "2_2") (pintype "passive"))
      (node (ref "J7") (pin "2") (pinfunction "2_2") (pintype "passive"))
      (node (ref "Q4") (pin "1") (pinfunction "S1_1") (pintype "passive"))
      (node (ref "Q4") (pin "2") (pinfunction "S2_2") (pintype "passive"))
      (node (ref "Q4") (pin "3") (pinfunction "S3_3") (pintype "passive"))
      (node (ref "Q5") (pin "5") (pinfunction "D_5") (pintype "passive"))
      (node (ref "Q5") (pin "6") (pinfunction "D6_6") (pintype "passive"))
      (node (ref "Q5") (pin "7") (pinfunction "D7_7") (pintype "passive"))
      (node (ref "Q5") (pin "8") (pinfunction "D8_8") (pintype "passive"))
      (node (ref "R41") (pin "2") (pinfunction "2_2") (pintype "passive"))
      (node (ref "R44") (pin "1") (pinfunction "1_1") (pintype "passive"))
      (node (ref "U11") (pin "6") (pinfunction "OUT_6") (pintype "passive"))
    )
    (net (code "33") (name "OUT3") (class "Default")
      (node (ref "C58") (pin "2") (pinfunction "2_2") (pintype "passive"))
      (node (ref "J7") (pin "1") (pinfunction "1_1") (pintype "passive"))
      (node (ref "Q6") (pin "1") (pinfunction "S1_1") (pintype "passive"))
      (node (ref "Q6") (pin "2") (pinfunction "S2_2") (pintype "passive"))
      (node (ref "Q6") (pin "3") (pinfunction "S3_3") (pintype "passive"))
      (node (ref "Q7") (pin "5") (pinfunction "D_5") (pintype "passive"))
      (node (ref "Q7") (pin "6") (pinfunction "D6_6") (pintype "passive"))
      (node (ref "Q7") (pin "7") (pinfunction "D7_7") (pintype "passive"))
      (node (ref "Q7") (pin "8") (pinfunction "D8_8") (pintype "passive"))
      (node (ref "R48") (pin "2") (pinfunction "2_2") (pintype "passive"))
      (node (ref "R51") (pin "1") (pinfunction "1_1") (pintype "passive"))
      (node (ref "U13") (pin "6") (pinfunction "OUT_6") (pintype "passive"))
    )
    (net (code "34") (name "TIM1_CH1") (class "Default")
      (node (ref "C48") (pin "1") (pinfunction "1_1") (pintype "passive"))
      (node (ref "U10") (pin "2") (pinfunction "HIN_2") (pintype "passive"))
    )
    (net (code "35") (name "TIM1_CH1N") (class "Default")
      (node (ref "C47") (pin "1") (pinfunction "1_1") (pintype "passive"))
      (node (ref "U10") (pin "1") (pinfunction "LIN_1") (pintype "passive"))
    )
    (net (code "36") (name "TIM1_CH2") (class "Default")
      (node (ref "C54") (pin "1") (pinfunction "1_1") (pintype "passive"))
      (node (ref "U11") (pin "2") (pinfunction "HIN_2") (pintype "passive"))
    )
    (net (code "37") (name "TIM1_CH2N") (class "Default")
      (node (ref "C53") (pin "1") (pinfunction "1_1") (pintype "passive"))
      (node (ref "U11") (pin "1") (pinfunction "LIN_1") (pintype "passive"))
    )
    (net (code "38") (name "TIM1_CH3") (class "Default")
      (node (ref "C61") (pin "1") (pinfunction "1_1") (pintype "passive"))
      (node (ref "U13") (pin "2") (pinfunction "HIN_2") (pintype "passive"))
    )
    (net (code "39") (name "TIM1_CH3N") (class "Default")
      (node (ref "C60") (pin "1") (pinfunction "1_1") (pintype "passive"))
      (node (ref "U13") (pin "1") (pinfunction "LIN_1") (pintype "passive"))
    )
    (net (code "40") (name "V+") (class "Default")
      (node (ref "C27") (pin "2") (pinfunction "2_2") (pintype "passive"))
      (node (ref "C28") (pin "2") (pinfunction "2_2") (pintype "passive"))
      (node (ref "C29") (pin "2") (pinfunction "2_2") (pintype "passive"))
      (node (ref "C30") (pin "2") (pinfunction "2_2") (pintype "passive"))
      (node (ref "C31") (pin "2") (pinfunction "2_2") (pintype "passive"))
      (node (ref "C32") (pin "2") (pinfunction "2_2") (pintype "passive"))
      (node (ref "C33") (pin "2") (pinfunction "2_2") (pintype "passive"))
      (node (ref "C34") (pin "2") (pinfunction "2_2") (pintype "passive"))
      (node (ref "C35") (pin "2") (pinfunction "2_2") (pintype "passive"))
      (node (ref "C36") (pin "2") (pinfunction "2_2") (pintype "passive"))
      (node (ref "C37") (pin "2") (pinfunction "2_2") (pintype "passive"))
      (node (ref "C38") (pin "2") (pinfunction "2_2") (pintype "passive"))
      (node (ref "C39") (pin "2") (pinfunction "2_2") (pintype "passive"))
      (node (ref "C40") (pin "2") (pinfunction "2_2") (pintype "passive"))
      (node (ref "C41") (pin "1") (pinfunction "1_1") (pintype "passive"))
      (node (ref "C44") (pin "1") (pinfunction "1_1") (pintype "passive"))
      (node (ref "D20") (pin "C") (pinfunction "C_C") (pintype "passive"))
      (node (ref "J5") (pin "1") (pinfunction "1_1") (pintype "passive"))
      (node (ref "Q2") (pin "5") (pinfunction "D_5") (pintype "passive"))
      (node (ref "Q2") (pin "6") (pinfunction "D6_6") (pintype "passive"))
      (node (ref "Q2") (pin "7") (pinfunction "D7_7") (pintype "passive"))
      (node (ref "Q2") (pin "8") (pinfunction "D8_8") (pintype "passive"))
      (node (ref "Q4") (pin "5") (pinfunction "D_5") (pintype "passive"))
      (node (ref "Q4") (pin "6") (pinfunction "D6_6") (pintype "passive"))
      (node (ref "Q4") (pin "7") (pinfunction "D7_7") (pintype "passive"))
      (node (ref "Q4") (pin "8") (pinfunction "D8_8") (pintype "passive"))
      (node (ref "Q6") (pin "5") (pinfunction "D_5") (pintype "passive"))
      (node (ref "Q6") (pin "6") (pinfunction "D6_6") (pintype "passive"))
      (node (ref "Q6") (pin "7") (pinfunction "D7_7") (pintype "passive"))
      (node (ref "Q6") (pin "8") (pinfunction "D8_8") (pintype "passive"))
      (node (ref "U9") (pin "10") (pinfunction "VCC10_10") (pintype "passive"))
      (node (ref "U9") (pin "4") (pinfunction "EN_4") (pintype "passive"))
      (node (ref "U9") (pin "9") (pinfunction "VCC9_9") (pintype "passive"))
    )
    (net (code "41") (name "Vshunt_1 +") (class "Default")
      (node (ref "Q3") (pin "1") (pinfunction "S1_1") (pintype "passive"))
      (node (ref "Q3") (pin "2") (pinfunction "S2_2") (pintype "passive"))
      (node (ref "Q3") (pin "3") (pinfunction "S3_3") (pintype "passive"))
      (node (ref "R39") (pin "2") (pinfunction "2_2") (pintype "passive"))
      (node (ref "R54") (pin "1") (pinfunction "1_1") (pintype "passive"))
    )
    (net (code "42") (name "Vshunt_1-") (class "Default")
      (node (ref "JP1") (pin "1") (pinfunction "1_1") (pintype "passive"))
    )
    (net (code "43") (name "Vshunt_2 +") (class "Default")
      (node (ref "Q5") (pin "1") (pinfunction "S1_1") (pintype "passive"))
      (node (ref "Q5") (pin "2") (pinfunction "S2_2") (pintype "passive"))
      (node (ref "Q5") (pin "3") (pinfunction "S3_3") (pintype "passive"))
      (node (ref "R45") (pin "2") (pinfunction "2_2") (pintype "passive"))
      (node (ref "R55") (pin "1") (pinfunction "1_1") (pintype "passive"))
    )
    (net (code "44") (name "Vshunt_2-") (class "Default")
      (node (ref "JP2") (pin "1") (pinfunction "1_1") (pintype "passive"))
    )
    (net (code "45") (name "Vshunt_3 +") (class "Default")
      (node (ref "Q7") (pin "1") (pinfunction "S1_1") (pintype "passive"))
      (node (ref "Q7") (pin "2") (pinfunction "S2_2") (pintype "passive"))
      (node (ref "Q7") (pin "3") (pinfunction "S3_3") (pintype "passive"))
      (node (ref "R52") (pin "2") (pinfunction "2_2") (pintype "passive"))
      (node (ref "R56") (pin "1") (pinfunction "1_1") (pintype "passive"))
    )
    (net (code "46") (name "Vshunt_3-") (class "Default")
      (node (ref "JP3") (pin "1") (pinfunction "1_1") (pintype "passive"))
    )
    (net (code "47") (name "unconnected-(U9-SYNC-Pad3)") (class "Default")
      (node (ref "U9") (pin "3") (pinfunction "SYNC_3") (pintype "passive+no_connect"))
    )
    (net (code "48") (name "unconnected-(U12-PG-Pad3)") (class "Default")
      (node (ref "U12") (pin "3") (pinfunction "PG_3") (pintype "passive+no_connect"))
    )
    (net (code "49") (name "unconnected-(U14-PG-Pad3)") (class "Default")
      (node (ref "U14") (pin "3") (pinfunction "PG_3") (pintype "passive+no_connect"))
    )
  )
)
